# ISO7741.net
KiCad netlist of a schematic drawn in Altium Designer
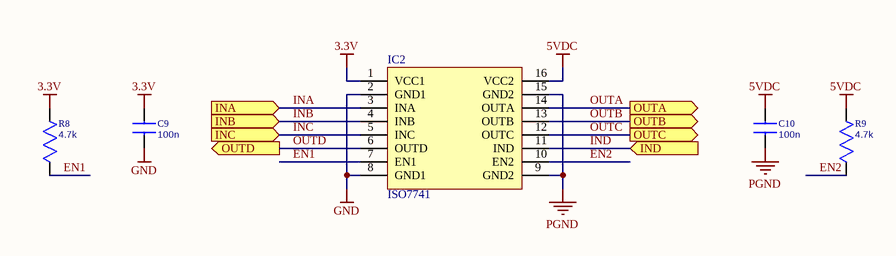
[diagram p0: ISO7741.SchDoc]

(export (version "E")
  (design (tool "Eeschema 10.0.6"))
  (components
    (comp (ref "C9")
      (value "100n")
      (footprint "C_0603")
      (description "Capacitor")
      (libsource (lib "AX_Altium_v2.3") (part "C0603"))
    )
    (comp (ref "C10")
      (value "100n")
      (footprint "C_0603")
      (description "Capacitor")
      (libsource (lib "AX_Altium_v2.3") (part "C0603"))
    )
    (comp (ref "IC2")
      (value "ISO7741")
      (footprint "SOIC-16")
      (description "Quad-Channel Digital Isolators")
      (libsource (lib "SmartOutletIntegratedLibrary") (part "ISO7741"))
    )
    (comp (ref "R8")
      (value "4.7k")
      (footprint "R_0603")
      (description "Resistor")
      (libsource (lib "AX_Altium_v2.3") (part "R0603"))
    )
    (comp (ref "R9")
      (value "4.7k")
      (footprint "R_0603")
      (description "Resistor")
      (libsource (lib "AX_Altium_v2.3") (part "R0603"))
    )
  )
  (nets
    (net (code "1") (name "/EN1") (class "Default")
      (node (ref "IC2") (pin "7") (pinfunction "EN1_7") (pintype "passive"))
      (node (ref "R8") (pin "1") (pintype "passive"))
    )
    (net (code "2") (name "/EN2") (class "Default")
      (node (ref "IC2") (pin "10") (pinfunction "EN2_10") (pintype "passive"))
      (node (ref "R9") (pin "1") (pintype "passive"))
    )
    (net (code "3") (name "/INA") (class "Default")
      (node (ref "IC2") (pin "3") (pinfunction "INA_3") (pintype "passive"))
    )
    (net (code "4") (name "/INB") (class "Default")
      (node (ref "IC2") (pin "4") (pinfunction "INB_4") (pintype "passive"))
    )
    (net (code "5") (name "/INC") (class "Default")
      (node (ref "IC2") (pin "5") (pinfunction "INC_5") (pintype "passive"))
    )
    (net (code "6") (name "/IND") (class "Default")
      (node (ref "IC2") (pin "11") (pinfunction "IND_11") (pintype "passive"))
    )
    (net (code "7") (name "/OUTA") (class "Default")
      (node (ref "IC2") (pin "14") (pinfunction "OUTA_14") (pintype "passive"))
    )
    (net (code "8") (name "/OUTB") (class "Default")
      (node (ref "IC2") (pin "13") (pinfunction "OUTB_13") (pintype "passive"))
    )
    (net (code "9") (name "/OUTC") (class "Default")
      (node (ref "IC2") (pin "12") (pinfunction "OUTC_12") (pintype "passive"))
    )
    (net (code "10") (name "/OUTD") (class "Default")
      (node (ref "IC2") (pin "6") (pinfunction "OUTD_6") (pintype "passive"))
    )
    (net (code "11") (name "3.3V") (class "Default")
      (node (ref "C9") (pin "2") (pintype "passive"))
      (node (ref "IC2") (pin "1") (pinfunction "VCC1_1") (pintype "passive"))
      (node (ref "R8") (pin "2") (pintype "passive"))
    )
    (net (code "12") (name "5VDC") (class "Default")
      (node (ref "C10") (pin "2") (pintype "passive"))
      (node (ref "IC2") (pin "16") (pinfunction "VCC2_16") (pintype "passive"))
      (node (ref "R9") (pin "2") (pintype "passive"))
    )
    (net (code "13") (name "GND") (class "Default")
      (node (ref "C9") (pin "1") (pintype "passive"))
      (node (ref "IC2") (pin "2") (pinfunction "GND1_2") (pintype "passive"))
      (node (ref "IC2") (pin "8") (pinfunction "GND1_8") (pintype "passive"))
    )
    (net (code "14") (name "PGND") (class "Default")
      (node (ref "C10") (pin "1") (pintype "passive"))
      (node (ref "IC2") (pin "15") (pinfunction "GND2_15") (pintype "passive"))
      (node (ref "IC2") (pin "9") (pinfunction "GND2_9") (pintype "passive"))
    )
  )
)
